# DriverBoardTest.net
KiCad netlist of a schematic drawn in EAGLE
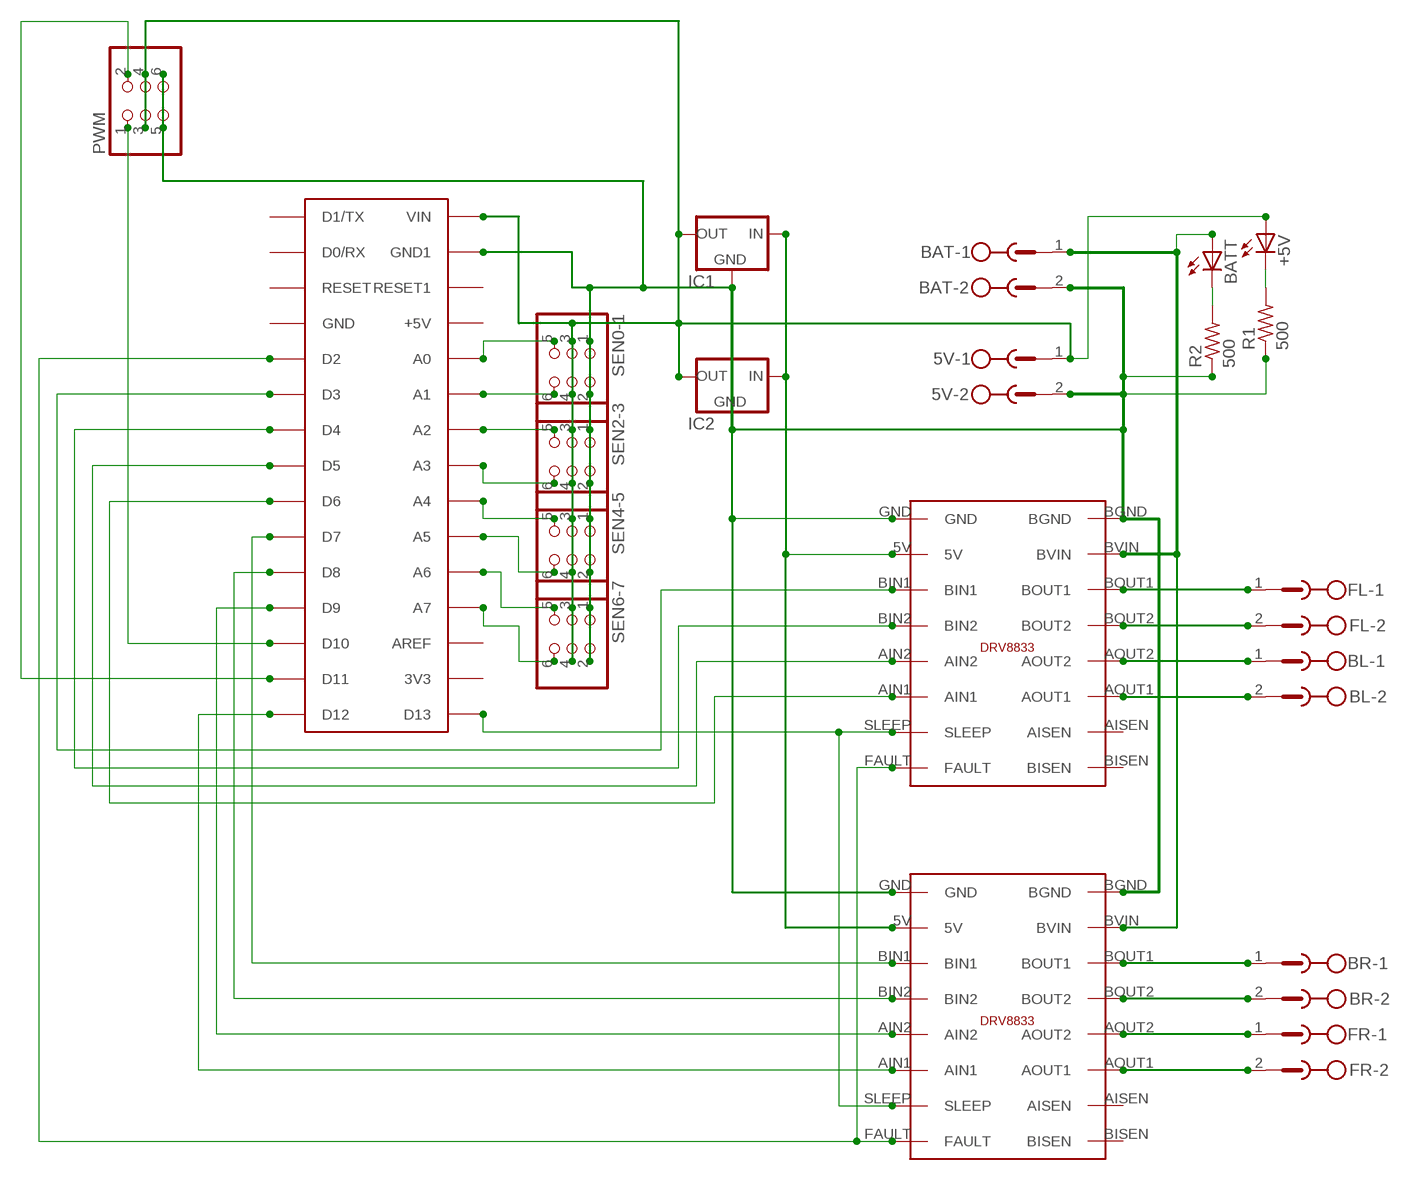
[diagram p0: schematic, sheet 1]

(export (version "E")
  (design (tool "Eeschema 10.0.6"))
  (components
    (comp (ref "+5V")
      (value "LED5MM")
      (footprint "eagle-import:LED5MM")
      (libsource (lib "eagle-import") (part "LED5MM"))
    )
    (comp (ref "5V")
      (value "MSTBV2")
      (footprint "eagle-import:MSTBV2")
      (libsource (lib "eagle-import") (part "MSTBV2"))
    )
    (comp (ref "BAT")
      (value "MSTBV2")
      (footprint "eagle-import:MSTBV2")
      (libsource (lib "eagle-import") (part "MSTBV2"))
    )
    (comp (ref "BATT")
      (value "LED5MM")
      (footprint "eagle-import:LED5MM")
      (libsource (lib "eagle-import") (part "LED5MM"))
    )
    (comp (ref "BL")
      (value "MSTBV2")
      (footprint "eagle-import:MSTBV2")
      (libsource (lib "eagle-import") (part "MSTBV2"))
    )
    (comp (ref "BR")
      (value "MSTBV2")
      (footprint "eagle-import:MSTBV2")
      (libsource (lib "eagle-import") (part "MSTBV2"))
    )
    (comp (ref "FL")
      (value "MSTBV2")
      (footprint "eagle-import:MSTBV2")
      (libsource (lib "eagle-import") (part "MSTBV2"))
    )
    (comp (ref "FR")
      (value "MSTBV2")
      (footprint "eagle-import:MSTBV2")
      (libsource (lib "eagle-import") (part "MSTBV2"))
    )
    (comp (ref "IC1")
      (value "78XXS")
      (footprint "eagle-import:78XXS")
      (libsource (lib "eagle-import") (part "78XXS"))
    )
    (comp (ref "IC2")
      (value "78XXS")
      (footprint "eagle-import:78XXS")
      (libsource (lib "eagle-import") (part "78XXS"))
    )
    (comp (ref "PWM")
      (value "PINHD-2X3")
      (footprint "eagle-import:2X03")
      (libsource (lib "eagle-import") (part "PINHD-2X3"))
    )
    (comp (ref "R1")
      (value "500")
      (footprint "eagle-import:0207_10")
      (libsource (lib "eagle-import") (part "R-US_0207/10"))
    )
    (comp (ref "R2")
      (value "500")
      (footprint "eagle-import:0207_10")
      (libsource (lib "eagle-import") (part "R-US_0207/10"))
    )
    (comp (ref "SEN0-1")
      (value "PINHD-2X3")
      (footprint "eagle-import:2X03")
      (libsource (lib "eagle-import") (part "PINHD-2X3"))
    )
    (comp (ref "SEN2-3")
      (value "PINHD-2X3")
      (footprint "eagle-import:2X03")
      (libsource (lib "eagle-import") (part "PINHD-2X3"))
    )
    (comp (ref "SEN4-5")
      (value "PINHD-2X3")
      (footprint "eagle-import:2X03")
      (libsource (lib "eagle-import") (part "PINHD-2X3"))
    )
    (comp (ref "SEN6-7")
      (value "PINHD-2X3")
      (footprint "eagle-import:2X03")
      (libsource (lib "eagle-import") (part "PINHD-2X3"))
    )
    (comp (ref "U$1")
      (value "ARDUINONANO")
      (footprint "eagle-import:PDIP-32")
      (libsource (lib "eagle-import") (part "ARDUINONANO"))
    )
    (comp (ref "U$2")
      (value "DRV8833")
      (footprint "eagle-import:DRV8833")
      (libsource (lib "eagle-import") (part "DRV8833"))
    )
    (comp (ref "U$3")
      (value "DRV8833")
      (footprint "eagle-import:DRV8833")
      (libsource (lib "eagle-import") (part "DRV8833"))
    )
  )
  (nets
    (net (code "1") (name "Net-(+5V-C)") (class "Default")
      (node (ref "+5V") (pin "K") (pinfunction "C_K") (pintype "passive"))
      (node (ref "R1") (pin "2") (pinfunction "2_2") (pintype "passive"))
    )
    (net (code "2") (name "Net-(5VA-SK)") (class "Default")
      (node (ref "+5V") (pin "A") (pinfunction "A_A") (pintype "passive"))
      (node (ref "5V") (pin "1") (pinfunction "SK_1") (pintype "passive"))
      (node (ref "IC1") (pin "OUT") (pinfunction "OUT_OUT") (pintype "passive"))
      (node (ref "IC2") (pin "OUT") (pinfunction "OUT_OUT") (pintype "passive"))
      (node (ref "PWM") (pin "3") (pinfunction "3_3") (pintype "passive"))
      (node (ref "PWM") (pin "4") (pinfunction "4_4") (pintype "passive"))
      (node (ref "SEN0-1") (pin "3") (pinfunction "3_3") (pintype "passive"))
      (node (ref "SEN0-1") (pin "4") (pinfunction "4_4") (pintype "passive"))
      (node (ref "SEN2-3") (pin "3") (pinfunction "3_3") (pintype "passive"))
      (node (ref "SEN2-3") (pin "4") (pinfunction "4_4") (pintype "passive"))
      (node (ref "SEN4-5") (pin "3") (pinfunction "3_3") (pintype "passive"))
      (node (ref "SEN4-5") (pin "4") (pinfunction "4_4") (pintype "passive"))
      (node (ref "SEN6-7") (pin "3") (pinfunction "3_3") (pintype "passive"))
      (node (ref "SEN6-7") (pin "4") (pinfunction "4_4") (pintype "passive"))
      (node (ref "U$1") (pin "VIN") (pinfunction "VIN_VIN") (pintype "bidirectional"))
    )
    (net (code "3") (name "Net-(5VB-SK)") (class "Default")
      (node (ref "5V") (pin "2") (pinfunction "SK_2") (pintype "passive"))
      (node (ref "BAT") (pin "2") (pinfunction "SK_2") (pintype "passive"))
      (node (ref "IC1") (pin "GND") (pinfunction "GND_GND") (pintype "input"))
      (node (ref "IC2") (pin "GND") (pinfunction "GND_GND") (pintype "input"))
      (node (ref "PWM") (pin "5") (pinfunction "5_5") (pintype "passive"))
      (node (ref "PWM") (pin "6") (pinfunction "6_6") (pintype "passive"))
      (node (ref "R1") (pin "1") (pinfunction "1_1") (pintype "passive"))
      (node (ref "R2") (pin "1") (pinfunction "1_1") (pintype "passive"))
      (node (ref "SEN0-1") (pin "1") (pinfunction "1_1") (pintype "passive"))
      (node (ref "SEN0-1") (pin "2") (pinfunction "2_2") (pintype "passive"))
      (node (ref "SEN2-3") (pin "1") (pinfunction "1_1") (pintype "passive"))
      (node (ref "SEN2-3") (pin "2") (pinfunction "2_2") (pintype "passive"))
      (node (ref "SEN4-5") (pin "1") (pinfunction "1_1") (pintype "passive"))
      (node (ref "SEN4-5") (pin "2") (pinfunction "2_2") (pintype "passive"))
      (node (ref "SEN6-7") (pin "1") (pinfunction "1_1") (pintype "passive"))
      (node (ref "SEN6-7") (pin "2") (pinfunction "2_2") (pintype "passive"))
      (node (ref "U$1") (pin "GND1") (pinfunction "GND1_GND1") (pintype "bidirectional"))
      (node (ref "U$2") (pin "BGND") (pinfunction "BGND_BGND") (pintype "bidirectional"))
      (node (ref "U$2") (pin "GND") (pinfunction "GND_GND") (pintype "bidirectional"))
      (node (ref "U$3") (pin "BGND") (pinfunction "BGND_BGND") (pintype "bidirectional"))
      (node (ref "U$3") (pin "GND") (pinfunction "GND_GND") (pintype "bidirectional"))
    )
    (net (code "4") (name "Net-(BATA-SK)") (class "Default")
      (node (ref "BAT") (pin "1") (pinfunction "SK_1") (pintype "passive"))
      (node (ref "BATT") (pin "A") (pinfunction "A_A") (pintype "passive"))
      (node (ref "U$2") (pin "BVIN") (pinfunction "BVIN_BVIN") (pintype "bidirectional"))
      (node (ref "U$3") (pin "BVIN") (pinfunction "BVIN_BVIN") (pintype "bidirectional"))
    )
    (net (code "5") (name "Net-(BATT-C)") (class "Default")
      (node (ref "BATT") (pin "K") (pinfunction "C_K") (pintype "passive"))
      (node (ref "R2") (pin "2") (pinfunction "2_2") (pintype "passive"))
    )
    (net (code "6") (name "Net-(BLA-SK)") (class "Default")
      (node (ref "BL") (pin "1") (pinfunction "SK_1") (pintype "passive"))
      (node (ref "U$2") (pin "AOUT2") (pinfunction "AOUT2_AOUT2") (pintype "bidirectional"))
    )
    (net (code "7") (name "Net-(BLB-SK)") (class "Default")
      (node (ref "BL") (pin "2") (pinfunction "SK_2") (pintype "passive"))
      (node (ref "U$2") (pin "AOUT1") (pinfunction "AOUT1_AOUT1") (pintype "bidirectional"))
    )
    (net (code "8") (name "Net-(BRA-SK)") (class "Default")
      (node (ref "BR") (pin "1") (pinfunction "SK_1") (pintype "passive"))
      (node (ref "U$3") (pin "BOUT1") (pinfunction "BOUT1_BOUT1") (pintype "bidirectional"))
    )
    (net (code "9") (name "Net-(BRB-SK)") (class "Default")
      (node (ref "BR") (pin "2") (pinfunction "SK_2") (pintype "passive"))
      (node (ref "U$3") (pin "BOUT2") (pinfunction "BOUT2_BOUT2") (pintype "bidirectional"))
    )
    (net (code "10") (name "Net-(FLA-SK)") (class "Default")
      (node (ref "FL") (pin "1") (pinfunction "SK_1") (pintype "passive"))
      (node (ref "U$2") (pin "BOUT1") (pinfunction "BOUT1_BOUT1") (pintype "bidirectional"))
    )
    (net (code "11") (name "Net-(FLB-SK)") (class "Default")
      (node (ref "FL") (pin "2") (pinfunction "SK_2") (pintype "passive"))
      (node (ref "U$2") (pin "BOUT2") (pinfunction "BOUT2_BOUT2") (pintype "bidirectional"))
    )
    (net (code "12") (name "Net-(FRA-SK)") (class "Default")
      (node (ref "FR") (pin "1") (pinfunction "SK_1") (pintype "passive"))
      (node (ref "U$3") (pin "AOUT2") (pinfunction "AOUT2_AOUT2") (pintype "bidirectional"))
    )
    (net (code "13") (name "Net-(FRB-SK)") (class "Default")
      (node (ref "FR") (pin "2") (pinfunction "SK_2") (pintype "passive"))
      (node (ref "U$3") (pin "AOUT1") (pinfunction "AOUT1_AOUT1") (pintype "bidirectional"))
    )
    (net (code "14") (name "Net-(IC1-PadIN)") (class "Default")
      (node (ref "IC1") (pin "IN") (pinfunction "IN_IN") (pintype "input"))
      (node (ref "IC2") (pin "IN") (pinfunction "IN_IN") (pintype "input"))
      (node (ref "U$2") (pin "5V") (pinfunction "5V_5V") (pintype "bidirectional"))
      (node (ref "U$3") (pin "5V") (pinfunction "5V_5V") (pintype "bidirectional"))
    )
    (net (code "15") (name "Net-(PWM-Pad1)") (class "Default")
      (node (ref "PWM") (pin "1") (pinfunction "1_1") (pintype "passive"))
      (node (ref "U$1") (pin "D10") (pinfunction "D10_D10") (pintype "bidirectional"))
    )
    (net (code "16") (name "Net-(PWM-Pad2)") (class "Default")
      (node (ref "PWM") (pin "2") (pinfunction "2_2") (pintype "passive"))
      (node (ref "U$1") (pin "D11") (pinfunction "D11_D11") (pintype "bidirectional"))
    )
    (net (code "17") (name "Net-(SEN0-1-Pad5)") (class "Default")
      (node (ref "SEN0-1") (pin "5") (pinfunction "5_5") (pintype "passive"))
      (node (ref "U$1") (pin "A0") (pinfunction "A0_A0") (pintype "bidirectional"))
    )
    (net (code "18") (name "Net-(SEN0-1-Pad6)") (class "Default")
      (node (ref "SEN0-1") (pin "6") (pinfunction "6_6") (pintype "passive"))
      (node (ref "U$1") (pin "A1") (pinfunction "A1_A1") (pintype "bidirectional"))
    )
    (net (code "19") (name "Net-(SEN2-3-Pad5)") (class "Default")
      (node (ref "SEN2-3") (pin "5") (pinfunction "5_5") (pintype "passive"))
      (node (ref "U$1") (pin "A2") (pinfunction "A2_A2") (pintype "bidirectional"))
    )
    (net (code "20") (name "Net-(SEN2-3-Pad6)") (class "Default")
      (node (ref "SEN2-3") (pin "6") (pinfunction "6_6") (pintype "passive"))
      (node (ref "U$1") (pin "A3") (pinfunction "A3_A3") (pintype "bidirectional"))
    )
    (net (code "21") (name "Net-(SEN4-5-Pad5)") (class "Default")
      (node (ref "SEN4-5") (pin "5") (pinfunction "5_5") (pintype "passive"))
      (node (ref "U$1") (pin "A4") (pinfunction "A4_A4") (pintype "bidirectional"))
    )
    (net (code "22") (name "Net-(SEN4-5-Pad6)") (class "Default")
      (node (ref "SEN4-5") (pin "6") (pinfunction "6_6") (pintype "passive"))
      (node (ref "U$1") (pin "A5") (pinfunction "A5_A5") (pintype "bidirectional"))
    )
    (net (code "23") (name "Net-(SEN6-7-Pad5)") (class "Default")
      (node (ref "SEN6-7") (pin "5") (pinfunction "5_5") (pintype "passive"))
      (node (ref "U$1") (pin "A6") (pinfunction "A6_A6") (pintype "bidirectional"))
    )
    (net (code "24") (name "Net-(SEN6-7-Pad6)") (class "Default")
      (node (ref "SEN6-7") (pin "6") (pinfunction "6_6") (pintype "passive"))
      (node (ref "U$1") (pin "A7") (pinfunction "A7_A7") (pintype "bidirectional"))
    )
    (net (code "25") (name "Net-(U$1-PadD2)") (class "Default")
      (node (ref "U$1") (pin "D2") (pinfunction "D2_D2") (pintype "bidirectional"))
      (node (ref "U$2") (pin "FAULT") (pinfunction "FAULT_FAULT") (pintype "bidirectional"))
      (node (ref "U$3") (pin "FAULT") (pinfunction "FAULT_FAULT") (pintype "bidirectional"))
    )
    (net (code "26") (name "Net-(U$1-PadD3)") (class "Default")
      (node (ref "U$1") (pin "D3") (pinfunction "D3_D3") (pintype "bidirectional"))
      (node (ref "U$2") (pin "BIN1") (pinfunction "BIN1_BIN1") (pintype "bidirectional"))
    )
    (net (code "27") (name "Net-(U$1-PadD4)") (class "Default")
      (node (ref "U$1") (pin "D4") (pinfunction "D4_D4") (pintype "bidirectional"))
      (node (ref "U$2") (pin "BIN2") (pinfunction "BIN2_BIN2") (pintype "bidirectional"))
    )
    (net (code "28") (name "Net-(U$1-PadD5)") (class "Default")
      (node (ref "U$1") (pin "D5") (pinfunction "D5_D5") (pintype "bidirectional"))
      (node (ref "U$2") (pin "AIN2") (pinfunction "AIN2_AIN2") (pintype "bidirectional"))
    )
    (net (code "29") (name "Net-(U$1-PadD6)") (class "Default")
      (node (ref "U$1") (pin "D6") (pinfunction "D6_D6") (pintype "bidirectional"))
      (node (ref "U$2") (pin "AIN1") (pinfunction "AIN1_AIN1") (pintype "bidirectional"))
    )
    (net (code "30") (name "Net-(U$1-PadD7)") (class "Default")
      (node (ref "U$1") (pin "D7") (pinfunction "D7_D7") (pintype "bidirectional"))
      (node (ref "U$3") (pin "BIN1") (pinfunction "BIN1_BIN1") (pintype "bidirectional"))
    )
    (net (code "31") (name "Net-(U$1-PadD8)") (class "Default")
      (node (ref "U$1") (pin "D8") (pinfunction "D8_D8") (pintype "bidirectional"))
      (node (ref "U$3") (pin "BIN2") (pinfunction "BIN2_BIN2") (pintype "bidirectional"))
    )
    (net (code "32") (name "Net-(U$1-PadD9)") (class "Default")
      (node (ref "U$1") (pin "D9") (pinfunction "D9_D9") (pintype "bidirectional"))
      (node (ref "U$3") (pin "AIN2") (pinfunction "AIN2_AIN2") (pintype "bidirectional"))
    )
    (net (code "33") (name "Net-(U$1-PadD12)") (class "Default")
      (node (ref "U$1") (pin "D12") (pinfunction "D12_D12") (pintype "bidirectional"))
      (node (ref "U$3") (pin "AIN1") (pinfunction "AIN1_AIN1") (pintype "bidirectional"))
    )
    (net (code "34") (name "Net-(U$1-PadD13)") (class "Default")
      (node (ref "U$1") (pin "D13") (pinfunction "D13_D13") (pintype "bidirectional"))
      (node (ref "U$2") (pin "SLEEP") (pinfunction "SLEEP_SLEEP") (pintype "bidirectional"))
      (node (ref "U$3") (pin "SLEEP") (pinfunction "SLEEP_SLEEP") (pintype "bidirectional"))
    )
    (net (code "35") (name "unconnected-(U$1-Pad+5V)") (class "Default")
      (node (ref "U$1") (pin "+5V") (pinfunction "+5V_+5V") (pintype "bidirectional"))
    )
    (net (code "36") (name "unconnected-(U$1-Pad3V3)") (class "Default")
      (node (ref "U$1") (pin "3V3") (pinfunction "3V3_3V3") (pintype "bidirectional"))
    )
    (net (code "37") (name "unconnected-(U$1-PadAREF)") (class "Default")
      (node (ref "U$1") (pin "AREF") (pinfunction "AREF_AREF") (pintype "bidirectional"))
    )
    (net (code "38") (name "unconnected-(U$1-PadD0{slash}RX)") (class "Default")
      (node (ref "U$1") (pin "D0/RX") (pinfunction "D0/RX_D0/RX") (pintype "bidirectional"))
    )
    (net (code "39") (name "unconnected-(U$1-PadD1{slash}TX)") (class "Default")
      (node (ref "U$1") (pin "D1/TX") (pinfunction "D1/TX_D1/TX") (pintype "bidirectional"))
    )
    (net (code "40") (name "unconnected-(U$1-PadGND)") (class "Default")
      (node (ref "U$1") (pin "GND") (pinfunction "GND_GND") (pintype "bidirectional"))
    )
    (net (code "41") (name "unconnected-(U$1-PadRESET)") (class "Default")
      (node (ref "U$1") (pin "RESET") (pinfunction "RESET_RESET") (pintype "bidirectional"))
    )
    (net (code "42") (name "unconnected-(U$1-PadRESET1)") (class "Default")
      (node (ref "U$1") (pin "RESET1") (pinfunction "RESET1_RESET1") (pintype "bidirectional"))
    )
    (net (code "43") (name "unconnected-(U$2-PadAISEN)") (class "Default")
      (node (ref "U$2") (pin "AISEN") (pinfunction "AISEN_AISEN") (pintype "bidirectional"))
    )
    (net (code "44") (name "unconnected-(U$2-PadBISEN)") (class "Default")
      (node (ref "U$2") (pin "BISEN") (pinfunction "BISEN_BISEN") (pintype "bidirectional"))
    )
    (net (code "45") (name "unconnected-(U$3-PadAISEN)") (class "Default")
      (node (ref "U$3") (pin "AISEN") (pinfunction "AISEN_AISEN") (pintype "bidirectional"))
    )
    (net (code "46") (name "unconnected-(U$3-PadBISEN)") (class "Default")
      (node (ref "U$3") (pin "BISEN") (pinfunction "BISEN_BISEN") (pintype "bidirectional"))
    )
  )
)
